# 24V_board.net
KiCad netlist of a schematic drawn in Altium Designer
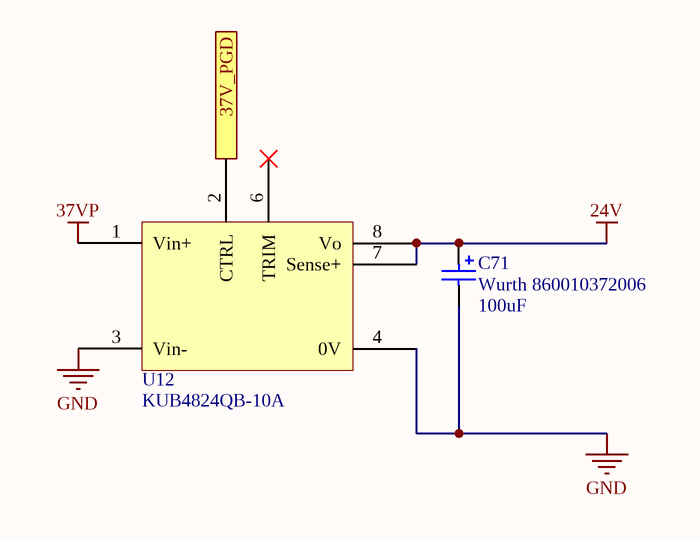
[diagram p0: 24V_board.SchDoc]

(export (version "E")
  (design (tool "Eeschema 10.0.6"))
  (components
    (comp (ref "C71")
      (value "Wurth 860010372006")
      (footprint "Wurth 860010372006")
      (description "Polarized Capacitor (Radial)")
      (fields (field (name "ALTIUM_VALUE") "100uF"))
      (libsource (lib "RSX_Capacitors") (part "Wurth 860010372006"))
    )
    (comp (ref "U12")
      (value "KUB4824QB-10A")
      (footprint "KUB48XXQB-10A")
      (description "12V 10A DC DC step down")
      (libsource (lib "RSX_ICs") (part "KUB4812QB-10A"))
    )
  )
  (nets
    (net (code "1") (name "/37V_PGD") (class "Default")
      (node (ref "U12") (pin "2") (pinfunction "CTRL_2") (pintype "passive"))
    )
    (net (code "2") (name "24V") (class "Default")
      (node (ref "C71") (pin "1") (pinfunction "1_1") (pintype "passive"))
      (node (ref "U12") (pin "7") (pinfunction "Sense+_7") (pintype "passive"))
      (node (ref "U12") (pin "8") (pinfunction "Vo_8") (pintype "passive"))
    )
    (net (code "3") (name "37VP") (class "Default")
      (node (ref "U12") (pin "1") (pinfunction "Vin+_1") (pintype "passive"))
    )
    (net (code "4") (name "GND") (class "Default")
      (node (ref "C71") (pin "2") (pinfunction "2_2") (pintype "passive"))
      (node (ref "U12") (pin "3") (pinfunction "Vin-_3") (pintype "passive"))
      (node (ref "U12") (pin "4") (pinfunction "0V_4") (pintype "passive"))
    )
    (net (code "5") (name "unconnected-(U12-TRIM-Pad6)") (class "Default")
      (node (ref "U12") (pin "6") (pinfunction "TRIM_6") (pintype "passive+no_connect"))
    )
  )
)
